# STM32F103C8T6.net
KiCad netlist of a schematic drawn in Altium Designer
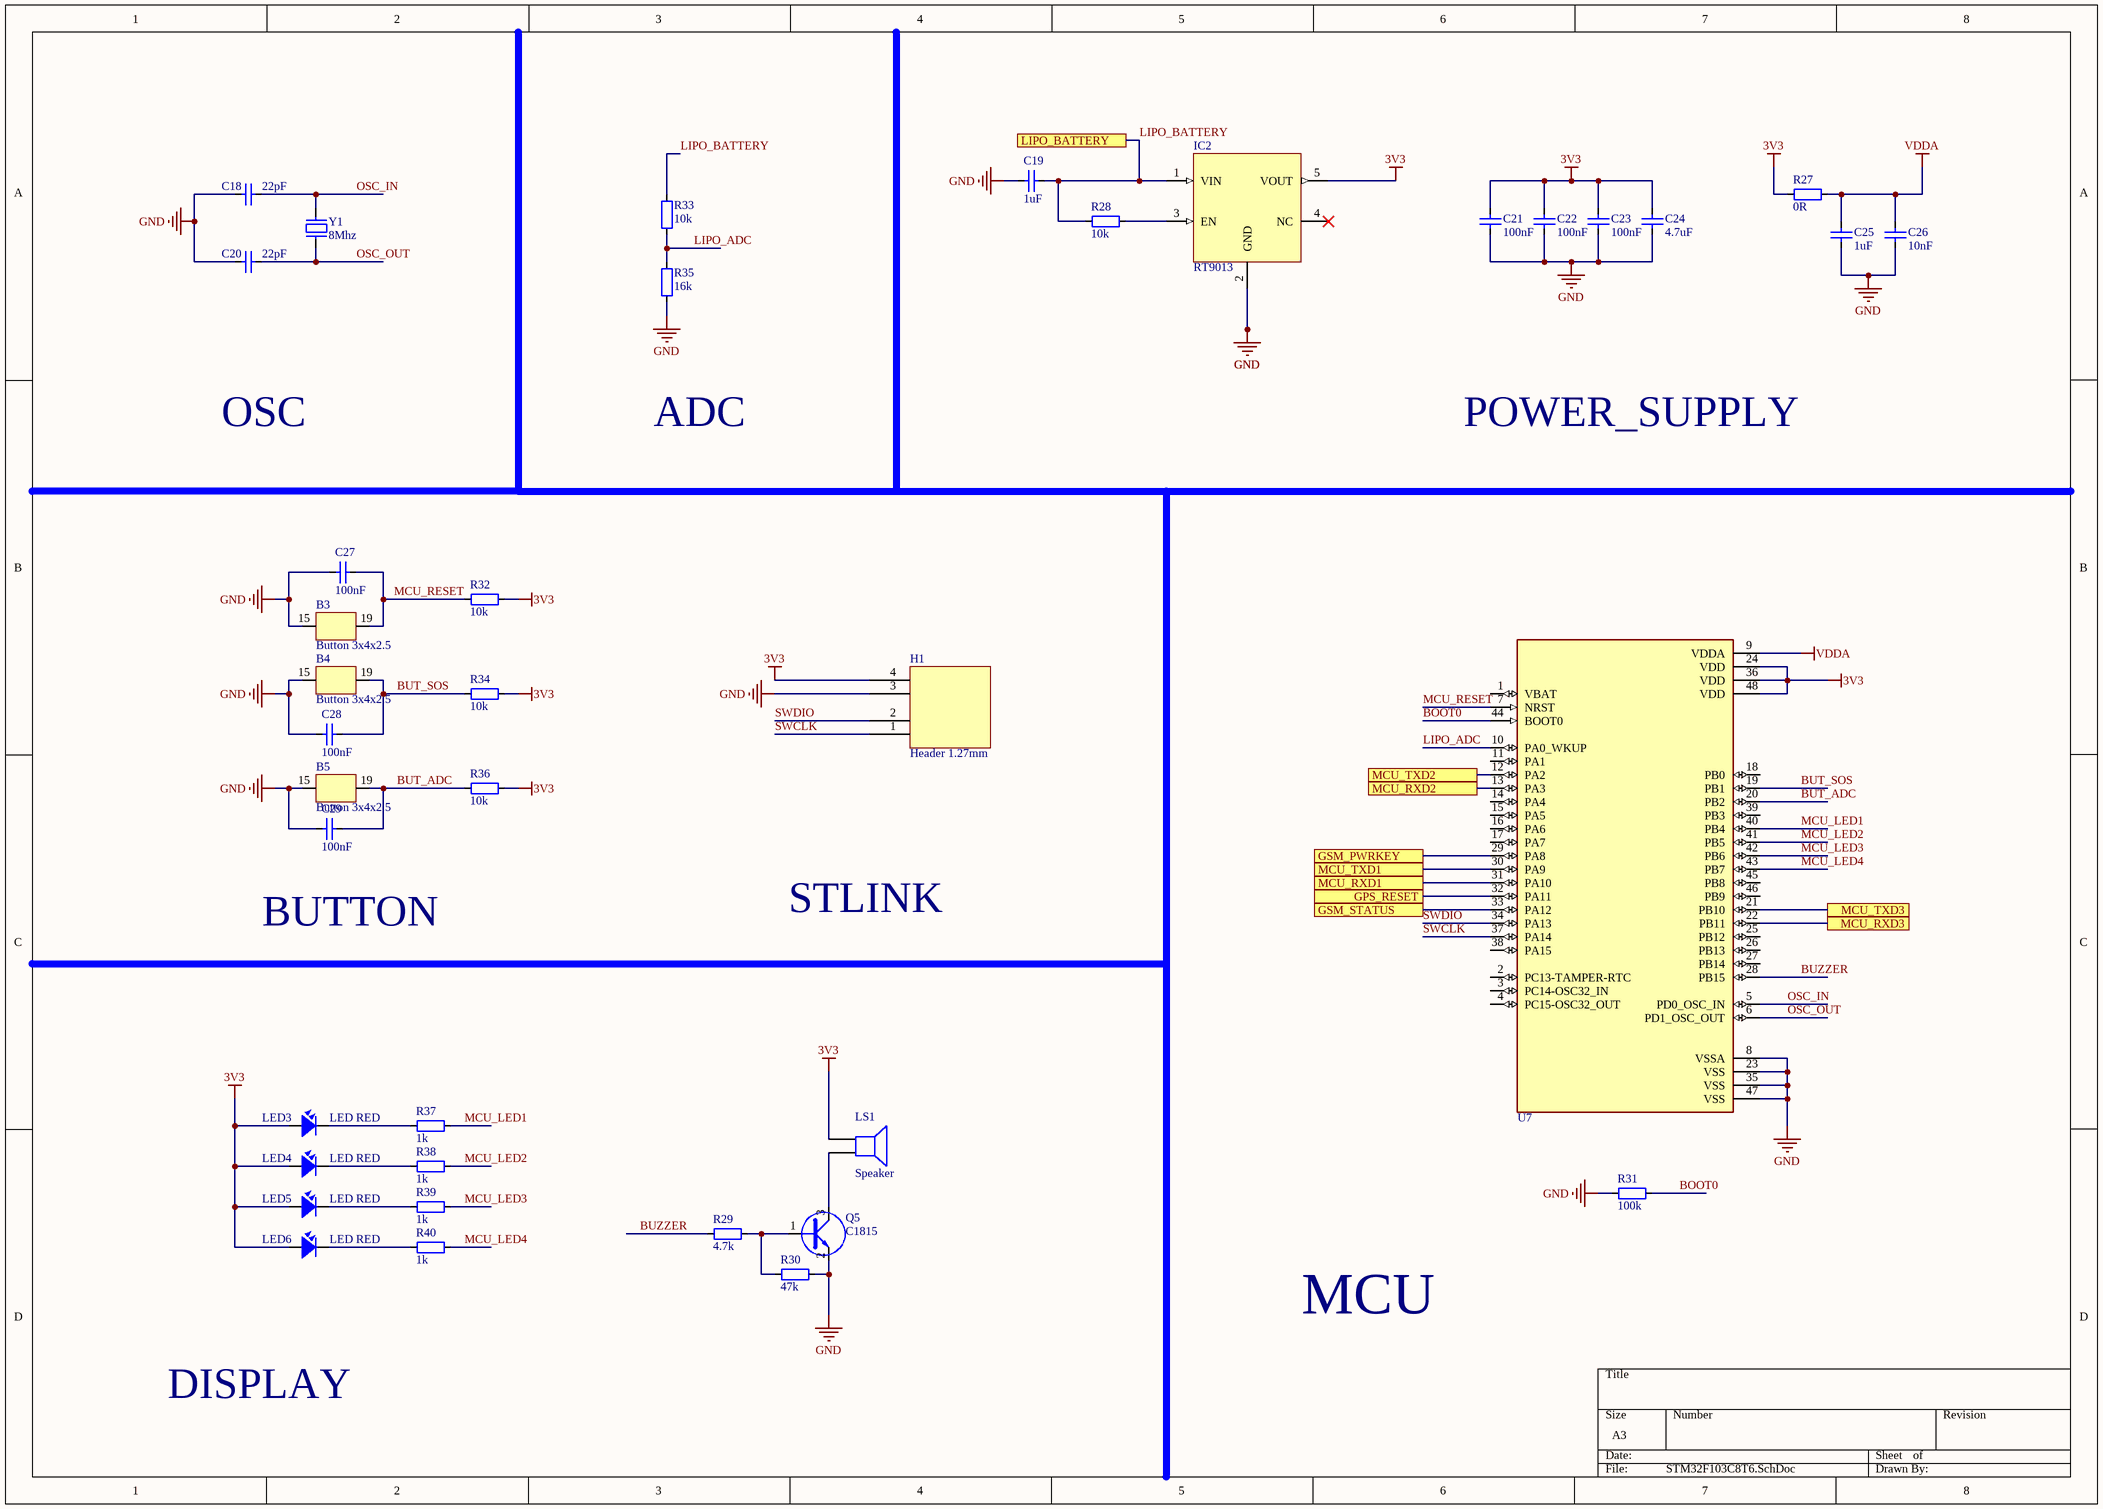
[diagram p0: STM32F103C8T6.SchDoc]

(export (version "E")
  (design (tool "Eeschema 10.0.6"))
  (components
    (comp (ref "B3")
      (value "Button 3x4x2.5")
      (footprint "Button 3x4x2.5")
      (libsource (lib "My Library") (part "Button 3x4x2.5"))
    )
    (comp (ref "B4")
      (value "Button 3x4x2.5")
      (footprint "Button 3x4x2.5")
      (libsource (lib "My Library") (part "Button 3x4x2.5"))
    )
    (comp (ref "B5")
      (value "Button 3x4x2.5")
      (footprint "Button 3x4x2.5")
      (libsource (lib "My Library") (part "Button 3x4x2.5"))
    )
    (comp (ref "C18")
      (value "22pF")
      (footprint "CAP_0805")
      (description "Capacitor")
      (fields (field (name "PUBLISHER") "Altium Limited"))
      (libsource (lib "My Library") (part "CapSMD"))
    )
    (comp (ref "C19")
      (value "1uF")
      (footprint "CAP_0805")
      (description "Capacitor")
      (fields (field (name "PUBLISHER") "Altium Limited"))
      (libsource (lib "My Library") (part "CapSMD"))
    )
    (comp (ref "C20")
      (value "22pF")
      (footprint "CAP_0805")
      (description "Capacitor")
      (fields (field (name "PUBLISHER") "Altium Limited"))
      (libsource (lib "My Library") (part "CapSMD"))
    )
    (comp (ref "C21")
      (value "100nF")
      (footprint "CAP_0805")
      (description "Capacitor")
      (fields (field (name "PUBLISHER") "Altium Limited"))
      (libsource (lib "My Library") (part "CapSMD"))
    )
    (comp (ref "C22")
      (value "100nF")
      (footprint "CAP_0805")
      (description "Capacitor")
      (fields (field (name "PUBLISHER") "Altium Limited"))
      (libsource (lib "My Library") (part "CapSMD"))
    )
    (comp (ref "C23")
      (value "100nF")
      (footprint "CAP_0805")
      (description "Capacitor")
      (fields (field (name "PUBLISHER") "Altium Limited"))
      (libsource (lib "My Library") (part "CapSMD"))
    )
    (comp (ref "C24")
      (value "4.7uF")
      (footprint "CAP_0805")
      (description "Capacitor")
      (fields (field (name "PUBLISHER") "Altium Limited"))
      (libsource (lib "My Library") (part "CapSMD"))
    )
    (comp (ref "C25")
      (value "1uF")
      (footprint "CAP_0805")
      (description "Capacitor")
      (fields (field (name "PUBLISHER") "Altium Limited"))
      (libsource (lib "My Library") (part "CapSMD"))
    )
    (comp (ref "C26")
      (value "10nF")
      (footprint "CAP_0805")
      (description "Capacitor")
      (fields (field (name "PUBLISHER") "Altium Limited"))
      (libsource (lib "My Library") (part "CapSMD"))
    )
    (comp (ref "C27")
      (value "100nF")
      (footprint "CAP_0805")
      (description "Capacitor")
      (fields (field (name "PUBLISHER") "Altium Limited"))
      (libsource (lib "My Library") (part "CapSMD"))
    )
    (comp (ref "C28")
      (value "100nF")
      (footprint "CAP_0805")
      (description "Capacitor")
      (fields (field (name "PUBLISHER") "Altium Limited"))
      (libsource (lib "My Library") (part "CapSMD"))
    )
    (comp (ref "C29")
      (value "100nF")
      (footprint "CAP_0805")
      (description "Capacitor")
      (fields (field (name "PUBLISHER") "Altium Limited"))
      (libsource (lib "My Library") (part "CapSMD"))
    )
    (comp (ref "H1")
      (value "Header 1.27mm")
      (footprint "Header 1.27mm")
      (libsource (lib "My Library") (part "Header 1.27mm"))
    )
    (comp (ref "IC2")
      (value "RT9013")
      (footprint "SOT23-5")
      (description "RT9013-33GB IC REG LINEAR 3.3V 500mA SOT23-5")
      (libsource (lib "My Library") (part "RT9013"))
    )
    (comp (ref "LED3")
      (value "LED RED")
      (footprint "LED-0805-Red")
      (description "LED Single colour Green and Red")
      (libsource (lib "My Library") (part "LED"))
    )
    (comp (ref "LED4")
      (value "LED RED")
      (footprint "LED-0805-Red")
      (description "LED Single colour Green and Red")
      (libsource (lib "My Library") (part "LED"))
    )
    (comp (ref "LED5")
      (value "LED RED")
      (footprint "LED-0805-Red")
      (description "LED Single colour Green and Red")
      (libsource (lib "My Library") (part "LED"))
    )
    (comp (ref "LED6")
      (value "LED RED")
      (footprint "LED-0805-Red")
      (description "LED Single colour Green and Red")
      (libsource (lib "My Library") (part "LED"))
    )
    (comp (ref "LS1")
      (value "Speaker")
      (footprint "SPEAKER")
      (description "Còi chíp 3V")
      (fields (field (name "PUBLISHER") "Altium Limited"))
      (libsource (lib "My Library") (part "Speaker"))
    )
    (comp (ref "Q5")
      (value "C1815")
      (footprint "SOT23D")
      (description "NPN 600mW, ECB")
      (libsource (lib "My Library") (part "2SC1815"))
    )
    (comp (ref "R27")
      (value "0R")
      (footprint "RES-SMD-0805")
      (description "Resistor")
      (fields
        (field (name "MANUFACTURER") "Generic Components")
        (field (name "PUBLISHER") "Altium Hobart Technology Centre")
      )
      (libsource (lib "My Library") (part "Resistor - SMD"))
    )
    (comp (ref "R28")
      (value "10k")
      (footprint "RES-SMD-0805")
      (description "Resistor")
      (fields
        (field (name "MANUFACTURER") "Generic Components")
        (field (name "PUBLISHER") "Altium Hobart Technology Centre")
      )
      (libsource (lib "My Library") (part "Resistor - SMD"))
    )
    (comp (ref "R29")
      (value "4.7k")
      (footprint "RES-SMD-0805")
      (description "Resistor")
      (fields
        (field (name "MANUFACTURER") "Generic Components")
        (field (name "PUBLISHER") "Altium Hobart Technology Centre")
      )
      (libsource (lib "My Library") (part "Resistor - SMD"))
    )
    (comp (ref "R30")
      (value "47k")
      (footprint "RES-SMD-0805")
      (description "Resistor")
      (fields
        (field (name "MANUFACTURER") "Generic Components")
        (field (name "PUBLISHER") "Altium Hobart Technology Centre")
      )
      (libsource (lib "My Library") (part "Resistor - SMD"))
    )
    (comp (ref "R31")
      (value "100k")
      (footprint "RES-SMD-0805")
      (description "Resistor")
      (fields
        (field (name "MANUFACTURER") "Generic Components")
        (field (name "PUBLISHER") "Altium Hobart Technology Centre")
      )
      (libsource (lib "My Library") (part "Resistor - SMD"))
    )
    (comp (ref "R32")
      (value "10k")
      (footprint "RES-SMD-0805")
      (description "Resistor")
      (fields
        (field (name "MANUFACTURER") "Generic Components")
        (field (name "PUBLISHER") "Altium Hobart Technology Centre")
      )
      (libsource (lib "My Library") (part "Resistor - SMD"))
    )
    (comp (ref "R33")
      (value "10k")
      (footprint "RES-SMD-0805")
      (description "Resistor")
      (fields
        (field (name "MANUFACTURER") "Generic Components")
        (field (name "PUBLISHER") "Altium Hobart Technology Centre")
      )
      (libsource (lib "My Library") (part "Resistor - SMD"))
    )
    (comp (ref "R34")
      (value "10k")
      (footprint "RES-SMD-0805")
      (description "Resistor")
      (fields
        (field (name "MANUFACTURER") "Generic Components")
        (field (name "PUBLISHER") "Altium Hobart Technology Centre")
      )
      (libsource (lib "My Library") (part "Resistor - SMD"))
    )
    (comp (ref "R35")
      (value "16k")
      (footprint "RES-SMD-0805")
      (description "Resistor")
      (fields
        (field (name "MANUFACTURER") "Generic Components")
        (field (name "PUBLISHER") "Altium Hobart Technology Centre")
      )
      (libsource (lib "My Library") (part "Resistor - SMD"))
    )
    (comp (ref "R36")
      (value "10k")
      (footprint "RES-SMD-0805")
      (description "Resistor")
      (fields
        (field (name "MANUFACTURER") "Generic Components")
        (field (name "PUBLISHER") "Altium Hobart Technology Centre")
      )
      (libsource (lib "My Library") (part "Resistor - SMD"))
    )
    (comp (ref "R37")
      (value "1k")
      (footprint "RES-SMD-0805")
      (description "Resistor")
      (fields
        (field (name "MANUFACTURER") "Generic Components")
        (field (name "PUBLISHER") "Altium Hobart Technology Centre")
      )
      (libsource (lib "My Library") (part "Resistor - SMD"))
    )
    (comp (ref "R38")
      (value "1k")
      (footprint "RES-SMD-0805")
      (description "Resistor")
      (fields
        (field (name "MANUFACTURER") "Generic Components")
        (field (name "PUBLISHER") "Altium Hobart Technology Centre")
      )
      (libsource (lib "My Library") (part "Resistor - SMD"))
    )
    (comp (ref "R39")
      (value "1k")
      (footprint "RES-SMD-0805")
      (description "Resistor")
      (fields
        (field (name "MANUFACTURER") "Generic Components")
        (field (name "PUBLISHER") "Altium Hobart Technology Centre")
      )
      (libsource (lib "My Library") (part "Resistor - SMD"))
    )
    (comp (ref "R40")
      (value "1k")
      (footprint "RES-SMD-0805")
      (description "Resistor")
      (fields
        (field (name "MANUFACTURER") "Generic Components")
        (field (name "PUBLISHER") "Altium Hobart Technology Centre")
      )
      (libsource (lib "My Library") (part "Resistor - SMD"))
    )
    (comp (ref "U7")
      (value "STM32")
      (footprint "LQFP 48")
      (description "STM32 ARM-based 32-bit MCU with 64 Kbytes Flash, 64-pin LQFP, Industrial Temperature")
      (libsource (lib "My Library") (part "STM32F103C8T6"))
    )
    (comp (ref "Y1")
      (value "8Mhz")
      (footprint "Thach Anh 2 chan SMD5032")
      (description "Crystal For all Crystal 2pin.")
      (libsource (lib "Altium_Lib_by_KhueNguyenCreator") (part "Thach Anh 2 chan SMD 5032"))
    )
  )
  (nets
    (net (code "1") (name "/BOOT0") (class "Default")
      (node (ref "R31") (pin "1") (pinfunction "1_1") (pintype "passive"))
      (node (ref "U7") (pin "44") (pinfunction "BOOT0_44") (pintype "input"))
    )
    (net (code "2") (name "/BUT_ADC") (class "Default")
      (node (ref "B5") (pin "19") (pinfunction "19_19") (pintype "passive"))
      (node (ref "C29") (pin "2") (pinfunction "2_2") (pintype "passive"))
      (node (ref "R36") (pin "2") (pinfunction "2_2") (pintype "passive"))
      (node (ref "U7") (pin "20") (pinfunction "PB2_20") (pintype "bidirectional"))
    )
    (net (code "3") (name "/BUT_SOS") (class "Default")
      (node (ref "B4") (pin "19") (pinfunction "19_19") (pintype "passive"))
      (node (ref "C28") (pin "2") (pinfunction "2_2") (pintype "passive"))
      (node (ref "R34") (pin "2") (pinfunction "2_2") (pintype "passive"))
      (node (ref "U7") (pin "19") (pinfunction "PB1_19") (pintype "bidirectional"))
    )
    (net (code "4") (name "/BUZZER") (class "Default")
      (node (ref "R29") (pin "1") (pinfunction "1_1") (pintype "passive"))
      (node (ref "U7") (pin "28") (pinfunction "PB15_28") (pintype "bidirectional"))
    )
    (net (code "5") (name "/GPS_RESET") (class "Default")
      (node (ref "U7") (pin "32") (pinfunction "PA11_32") (pintype "bidirectional"))
    )
    (net (code "6") (name "/GSM_PWRKEY") (class "Default")
      (node (ref "U7") (pin "29") (pinfunction "PA8_29") (pintype "bidirectional"))
    )
    (net (code "7") (name "/GSM_STATUS") (class "Default")
      (node (ref "U7") (pin "33") (pinfunction "PA12_33") (pintype "bidirectional"))
    )
    (net (code "8") (name "/LIPO_ADC") (class "Default")
      (node (ref "R33") (pin "2") (pinfunction "2_2") (pintype "passive"))
      (node (ref "R35") (pin "1") (pinfunction "1_1") (pintype "passive"))
      (node (ref "U7") (pin "10") (pinfunction "PA0_WKUP_10") (pintype "bidirectional"))
    )
    (net (code "9") (name "/LIPO_BATTERY") (class "Default")
      (node (ref "C19") (pin "2") (pinfunction "2_2") (pintype "passive"))
      (node (ref "IC2") (pin "1") (pinfunction "VIN_1") (pintype "input"))
      (node (ref "R28") (pin "2") (pinfunction "2_2") (pintype "passive"))
      (node (ref "R33") (pin "1") (pinfunction "1_1") (pintype "passive"))
    )
    (net (code "10") (name "/MCU_LED1") (class "Default")
      (node (ref "R37") (pin "1") (pinfunction "1_1") (pintype "passive"))
      (node (ref "U7") (pin "40") (pinfunction "PB4_40") (pintype "bidirectional"))
    )
    (net (code "11") (name "/MCU_LED2") (class "Default")
      (node (ref "R38") (pin "1") (pinfunction "1_1") (pintype "passive"))
      (node (ref "U7") (pin "41") (pinfunction "PB5_41") (pintype "bidirectional"))
    )
    (net (code "12") (name "/MCU_LED3") (class "Default")
      (node (ref "R39") (pin "1") (pinfunction "1_1") (pintype "passive"))
      (node (ref "U7") (pin "42") (pinfunction "PB6_42") (pintype "bidirectional"))
    )
    (net (code "13") (name "/MCU_LED4") (class "Default")
      (node (ref "R40") (pin "1") (pinfunction "1_1") (pintype "passive"))
      (node (ref "U7") (pin "43") (pinfunction "PB7_43") (pintype "bidirectional"))
    )
    (net (code "14") (name "/MCU_RESET") (class "Default")
      (node (ref "B3") (pin "19") (pinfunction "19_19") (pintype "passive"))
      (node (ref "C27") (pin "2") (pinfunction "2_2") (pintype "passive"))
      (node (ref "R32") (pin "2") (pinfunction "2_2") (pintype "passive"))
      (node (ref "U7") (pin "7") (pinfunction "NRST_7") (pintype "input"))
    )
    (net (code "15") (name "/MCU_RXD1") (class "Default")
      (node (ref "U7") (pin "31") (pinfunction "PA10_31") (pintype "bidirectional"))
    )
    (net (code "16") (name "/MCU_RXD2") (class "Default")
      (node (ref "U7") (pin "13") (pinfunction "PA3_13") (pintype "bidirectional"))
    )
    (net (code "17") (name "/MCU_RXD3") (class "Default")
      (node (ref "U7") (pin "22") (pinfunction "PB11_22") (pintype "bidirectional"))
    )
    (net (code "18") (name "/MCU_TXD1") (class "Default")
      (node (ref "U7") (pin "30") (pinfunction "PA9_30") (pintype "bidirectional"))
    )
    (net (code "19") (name "/MCU_TXD2") (class "Default")
      (node (ref "U7") (pin "12") (pinfunction "PA2_12") (pintype "bidirectional"))
    )
    (net (code "20") (name "/MCU_TXD3") (class "Default")
      (node (ref "U7") (pin "21") (pinfunction "PB10_21") (pintype "bidirectional"))
    )
    (net (code "21") (name "/OSC_IN") (class "Default")
      (node (ref "C18") (pin "2") (pinfunction "2_2") (pintype "passive"))
      (node (ref "U7") (pin "5") (pinfunction "PD0_OSC_IN_5") (pintype "bidirectional"))
      (node (ref "Y1") (pin "2") (pinfunction "2_2") (pintype "passive"))
    )
    (net (code "22") (name "/OSC_OUT") (class "Default")
      (node (ref "C20") (pin "2") (pinfunction "2_2") (pintype "passive"))
      (node (ref "U7") (pin "6") (pinfunction "PD1_OSC_OUT_6") (pintype "bidirectional"))
      (node (ref "Y1") (pin "1") (pinfunction "1_1") (pintype "passive"))
    )
    (net (code "23") (name "/SWCLK") (class "Default")
      (node (ref "H1") (pin "1") (pinfunction "1_1") (pintype "passive"))
      (node (ref "U7") (pin "37") (pinfunction "PA14_37") (pintype "bidirectional"))
    )
    (net (code "24") (name "/SWDIO") (class "Default")
      (node (ref "H1") (pin "2") (pinfunction "2_2") (pintype "passive"))
      (node (ref "U7") (pin "34") (pinfunction "PA13_34") (pintype "bidirectional"))
    )
    (net (code "25") (name "3V3") (class "Default")
      (node (ref "C21") (pin "2") (pinfunction "2_2") (pintype "passive"))
      (node (ref "C22") (pin "2") (pinfunction "2_2") (pintype "passive"))
      (node (ref "C23") (pin "2") (pinfunction "2_2") (pintype "passive"))
      (node (ref "C24") (pin "2") (pinfunction "2_2") (pintype "passive"))
      (node (ref "H1") (pin "4") (pinfunction "4_4") (pintype "passive"))
      (node (ref "IC2") (pin "5") (pinfunction "VOUT_5") (pintype "output"))
      (node (ref "LED3") (pin "1") (pinfunction "1_1") (pintype "passive"))
      (node (ref "LED4") (pin "1") (pinfunction "1_1") (pintype "passive"))
      (node (ref "LED5") (pin "1") (pinfunction "1_1") (pintype "passive"))
      (node (ref "LED6") (pin "1") (pinfunction "1_1") (pintype "passive"))
      (node (ref "LS1") (pin "1") (pinfunction "1_1") (pintype "passive"))
      (node (ref "R27") (pin "2") (pinfunction "2_2") (pintype "passive"))
      (node (ref "R32") (pin "1") (pinfunction "1_1") (pintype "passive"))
      (node (ref "R34") (pin "1") (pinfunction "1_1") (pintype "passive"))
      (node (ref "R36") (pin "1") (pinfunction "1_1") (pintype "passive"))
      (node (ref "U7") (pin "24") (pinfunction "VDD_24") (pintype "power_in"))
      (node (ref "U7") (pin "36") (pinfunction "VDD_36") (pintype "power_in"))
      (node (ref "U7") (pin "48") (pinfunction "VDD_48") (pintype "power_in"))
    )
    (net (code "26") (name "GND") (class "Default")
      (node (ref "B3") (pin "15") (pinfunction "15_15") (pintype "passive"))
      (node (ref "B4") (pin "15") (pinfunction "15_15") (pintype "passive"))
      (node (ref "B5") (pin "15") (pinfunction "15_15") (pintype "passive"))
      (node (ref "C18") (pin "1") (pinfunction "1_1") (pintype "passive"))
      (node (ref "C19") (pin "1") (pinfunction "1_1") (pintype "passive"))
      (node (ref "C20") (pin "1") (pinfunction "1_1") (pintype "passive"))
      (node (ref "C21") (pin "1") (pinfunction "1_1") (pintype "passive"))
      (node (ref "C22") (pin "1") (pinfunction "1_1") (pintype "passive"))
      (node (ref "C23") (pin "1") (pinfunction "1_1") (pintype "passive"))
      (node (ref "C24") (pin "1") (pinfunction "1_1") (pintype "passive"))
      (node (ref "C25") (pin "1") (pinfunction "1_1") (pintype "passive"))
      (node (ref "C26") (pin "1") (pinfunction "1_1") (pintype "passive"))
      (node (ref "C27") (pin "1") (pinfunction "1_1") (pintype "passive"))
      (node (ref "C28") (pin "1") (pinfunction "1_1") (pintype "passive"))
      (node (ref "C29") (pin "1") (pinfunction "1_1") (pintype "passive"))
      (node (ref "H1") (pin "3") (pinfunction "3_3") (pintype "passive"))
      (node (ref "IC2") (pin "2") (pinfunction "GND_2") (pintype "passive"))
      (node (ref "Q5") (pin "2") (pinfunction "E_2") (pintype "passive"))
      (node (ref "R30") (pin "2") (pinfunction "2_2") (pintype "passive"))
      (node (ref "R31") (pin "2") (pinfunction "2_2") (pintype "passive"))
      (node (ref "R35") (pin "2") (pinfunction "2_2") (pintype "passive"))
      (node (ref "U7") (pin "23") (pinfunction "VSS_23") (pintype "power_in"))
      (node (ref "U7") (pin "35") (pinfunction "VSS_35") (pintype "power_in"))
      (node (ref "U7") (pin "47") (pinfunction "VSS_47") (pintype "power_in"))
      (node (ref "U7") (pin "8") (pinfunction "VSSA_8") (pintype "power_in"))
    )
    (net (code "27") (name "Net-(IC2-EN)") (class "Default")
      (node (ref "IC2") (pin "3") (pinfunction "EN_3") (pintype "input"))
      (node (ref "R28") (pin "1") (pinfunction "1_1") (pintype "passive"))
    )
    (net (code "28") (name "Net-(LED3-Pad2)") (class "Default")
      (node (ref "LED3") (pin "2") (pinfunction "2_2") (pintype "passive"))
      (node (ref "R37") (pin "2") (pinfunction "2_2") (pintype "passive"))
    )
    (net (code "29") (name "Net-(LED4-Pad2)") (class "Default")
      (node (ref "LED4") (pin "2") (pinfunction "2_2") (pintype "passive"))
      (node (ref "R38") (pin "2") (pinfunction "2_2") (pintype "passive"))
    )
    (net (code "30") (name "Net-(LED5-Pad2)") (class "Default")
      (node (ref "LED5") (pin "2") (pinfunction "2_2") (pintype "passive"))
      (node (ref "R39") (pin "2") (pinfunction "2_2") (pintype "passive"))
    )
    (net (code "31") (name "Net-(LED6-Pad2)") (class "Default")
      (node (ref "LED6") (pin "2") (pinfunction "2_2") (pintype "passive"))
      (node (ref "R40") (pin "2") (pinfunction "2_2") (pintype "passive"))
    )
    (net (code "32") (name "Net-(Q5-B)") (class "Default")
      (node (ref "Q5") (pin "1") (pinfunction "B_1") (pintype "passive"))
      (node (ref "R29") (pin "2") (pinfunction "2_2") (pintype "passive"))
      (node (ref "R30") (pin "1") (pinfunction "1_1") (pintype "passive"))
    )
    (net (code "33") (name "Net-(Q5-C)") (class "Default")
      (node (ref "LS1") (pin "2") (pinfunction "2_2") (pintype "passive"))
      (node (ref "Q5") (pin "3") (pinfunction "C_3") (pintype "passive"))
    )
    (net (code "34") (name "VDDA") (class "Default")
      (node (ref "C25") (pin "2") (pinfunction "2_2") (pintype "passive"))
      (node (ref "C26") (pin "2") (pinfunction "2_2") (pintype "passive"))
      (node (ref "R27") (pin "1") (pinfunction "1_1") (pintype "passive"))
      (node (ref "U7") (pin "9") (pinfunction "VDDA_9") (pintype "power_in"))
    )
    (net (code "35") (name "unconnected-(IC2-NC-Pad4)") (class "Default")
      (node (ref "IC2") (pin "4") (pinfunction "NC_4") (pintype "passive+no_connect"))
    )
    (net (code "36") (name "unconnected-(U7-PA1-Pad11)") (class "Default")
      (node (ref "U7") (pin "11") (pinfunction "PA1_11") (pintype "bidirectional"))
    )
    (net (code "37") (name "unconnected-(U7-PA4-Pad14)") (class "Default")
      (node (ref "U7") (pin "14") (pinfunction "PA4_14") (pintype "bidirectional"))
    )
    (net (code "38") (name "unconnected-(U7-PA5-Pad15)") (class "Default")
      (node (ref "U7") (pin "15") (pinfunction "PA5_15") (pintype "bidirectional"))
    )
    (net (code "39") (name "unconnected-(U7-PA6-Pad16)") (class "Default")
      (node (ref "U7") (pin "16") (pinfunction "PA6_16") (pintype "bidirectional"))
    )
    (net (code "40") (name "unconnected-(U7-PA7-Pad17)") (class "Default")
      (node (ref "U7") (pin "17") (pinfunction "PA7_17") (pintype "bidirectional"))
    )
    (net (code "41") (name "unconnected-(U7-PA15-Pad38)") (class "Default")
      (node (ref "U7") (pin "38") (pinfunction "PA15_38") (pintype "bidirectional"))
    )
    (net (code "42") (name "unconnected-(U7-PB0-Pad18)") (class "Default")
      (node (ref "U7") (pin "18") (pinfunction "PB0_18") (pintype "bidirectional"))
    )
    (net (code "43") (name "unconnected-(U7-PB3-Pad39)") (class "Default")
      (node (ref "U7") (pin "39") (pinfunction "PB3_39") (pintype "bidirectional"))
    )
    (net (code "44") (name "unconnected-(U7-PB8-Pad45)") (class "Default")
      (node (ref "U7") (pin "45") (pinfunction "PB8_45") (pintype "bidirectional"))
    )
    (net (code "45") (name "unconnected-(U7-PB9-Pad46)") (class "Default")
      (node (ref "U7") (pin "46") (pinfunction "PB9_46") (pintype "bidirectional"))
    )
    (net (code "46") (name "unconnected-(U7-PB12-Pad25)") (class "Default")
      (node (ref "U7") (pin "25") (pinfunction "PB12_25") (pintype "bidirectional"))
    )
    (net (code "47") (name "unconnected-(U7-PB13-Pad26)") (class "Default")
      (node (ref "U7") (pin "26") (pinfunction "PB13_26") (pintype "bidirectional"))
    )
    (net (code "48") (name "unconnected-(U7-PB14-Pad27)") (class "Default")
      (node (ref "U7") (pin "27") (pinfunction "PB14_27") (pintype "bidirectional"))
    )
    (net (code "49") (name "unconnected-(U7-PC13-TAMPER-RTC-Pad2)") (class "Default")
      (node (ref "U7") (pin "2") (pinfunction "PC13-TAMPER-RTC_2") (pintype "bidirectional"))
    )
    (net (code "50") (name "unconnected-(U7-PC14-OSC32_IN-Pad3)") (class "Default")
      (node (ref "U7") (pin "3") (pinfunction "PC14-OSC32_IN_3") (pintype "bidirectional"))
    )
    (net (code "51") (name "unconnected-(U7-PC15-OSC32_OUT-Pad4)") (class "Default")
      (node (ref "U7") (pin "4") (pinfunction "PC15-OSC32_OUT_4") (pintype "bidirectional"))
    )
    (net (code "52") (name "unconnected-(U7-VBAT-Pad1)") (class "Default")
      (node (ref "U7") (pin "1") (pinfunction "VBAT_1") (pintype "bidirectional"))
    )
  )
)
